# Sheet1.net
KiCad netlist of a schematic drawn in Altium Designer
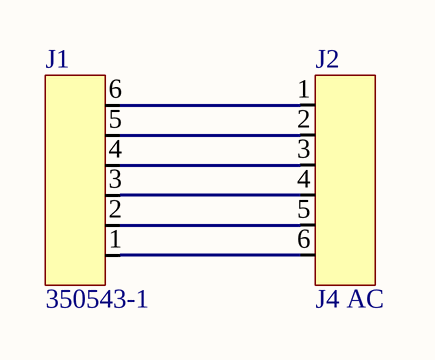
[diagram p0: Sheet1.SchDoc]

(export (version "E")
  (design (tool "Eeschema 10.0.6"))
  (components
    (comp (ref "J1")
      (value "350543-1")
      (footprint "TE_350543-1")
      (fields (field (name "MF") "{'manufacturer': u'TE Connectivity'}"))
      (libsource (lib "350543-1") (part "350543-1"))
    )
    (comp (ref "J2") (value "J4 AC") (footprint "J4 AC") (libsource (lib "Schlib1") (part "J4 AC")))
  )
  (nets
    (net (code "1") (name "Net-(J1-Pad1)") (class "Default")
      (node (ref "J1") (pin "1") (pintype "passive"))
      (node (ref "J2") (pin "6") (pintype "passive"))
    )
    (net (code "2") (name "Net-(J1-Pad2)") (class "Default")
      (node (ref "J1") (pin "2") (pintype "passive"))
      (node (ref "J2") (pin "5") (pintype "passive"))
    )
    (net (code "3") (name "Net-(J1-Pad3)") (class "Default")
      (node (ref "J1") (pin "3") (pintype "passive"))
      (node (ref "J2") (pin "4") (pintype "passive"))
    )
    (net (code "4") (name "Net-(J1-Pad4)") (class "Default")
      (node (ref "J1") (pin "4") (pintype "passive"))
      (node (ref "J2") (pin "3") (pintype "passive"))
    )
    (net (code "5") (name "Net-(J1-Pad5)") (class "Default")
      (node (ref "J1") (pin "5") (pintype "passive"))
      (node (ref "J2") (pin "2") (pintype "passive"))
    )
    (net (code "6") (name "Net-(J1-Pad6)") (class "Default")
      (node (ref "J1") (pin "6") (pintype "passive"))
      (node (ref "J2") (pin "1") (pintype "passive"))
    )
  )
)
